# brainslug_board_1.net
KiCad netlist of a schematic drawn in EAGLE
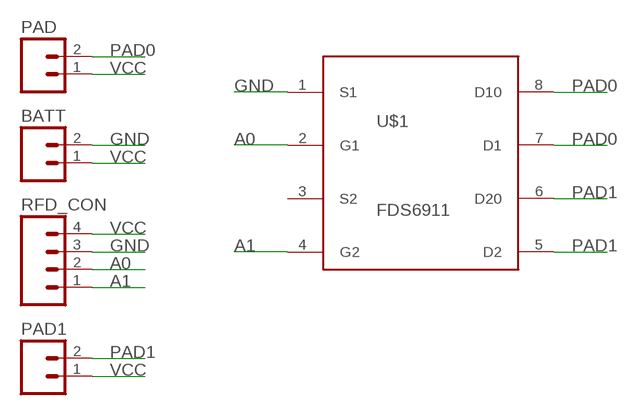
[diagram p0: schematic, sheet 1]

(export (version "E")
  (design (tool "Eeschema 10.0.6"))
  (components
    (comp (ref "BATT")
      (value "M02PTH")
      (footprint "eagle-import:1X02")
      (libsource (lib "eagle-import") (part "M02PTH"))
    )
    (comp (ref "PAD")
      (value "M02PTH")
      (footprint "eagle-import:1X02")
      (libsource (lib "eagle-import") (part "M02PTH"))
    )
    (comp (ref "PAD1")
      (value "M02PTH")
      (footprint "eagle-import:1X02")
      (libsource (lib "eagle-import") (part "M02PTH"))
    )
    (comp (ref "RFD_CON")
      (value "M04PTH")
      (footprint "eagle-import:1X04")
      (libsource (lib "eagle-import") (part "M04PTH"))
    )
    (comp (ref "U$1")
      (value "FDS6911")
      (footprint "eagle-import:SO8")
      (libsource (lib "eagle-import") (part "FDS6911"))
    )
  )
  (nets
    (net (code "1") (name "/A0") (class "Default")
      (node (ref "RFD_CON") (pin "2") (pinfunction "2_2") (pintype "passive"))
      (node (ref "U$1") (pin "2") (pinfunction "G1_2") (pintype "bidirectional"))
    )
    (net (code "2") (name "/A1") (class "Default")
      (node (ref "RFD_CON") (pin "1") (pinfunction "1_1") (pintype "passive"))
      (node (ref "U$1") (pin "4") (pinfunction "G2_4") (pintype "bidirectional"))
    )
    (net (code "3") (name "/GND") (class "Default")
      (node (ref "BATT") (pin "2") (pinfunction "2_2") (pintype "passive"))
      (node (ref "RFD_CON") (pin "3") (pinfunction "3_3") (pintype "passive"))
      (node (ref "U$1") (pin "1") (pinfunction "S1_1") (pintype "bidirectional"))
    )
    (net (code "4") (name "/PAD0") (class "Default")
      (node (ref "PAD") (pin "2") (pinfunction "2_2") (pintype "passive"))
      (node (ref "U$1") (pin "7") (pinfunction "D1_7") (pintype "bidirectional"))
      (node (ref "U$1") (pin "8") (pinfunction "D10_8") (pintype "bidirectional"))
    )
    (net (code "5") (name "/PAD1") (class "Default")
      (node (ref "PAD1") (pin "2") (pinfunction "2_2") (pintype "passive"))
      (node (ref "U$1") (pin "5") (pinfunction "D2_5") (pintype "bidirectional"))
      (node (ref "U$1") (pin "6") (pinfunction "D20_6") (pintype "bidirectional"))
    )
    (net (code "6") (name "/VCC") (class "Default")
      (node (ref "BATT") (pin "1") (pinfunction "1_1") (pintype "passive"))
      (node (ref "PAD") (pin "1") (pinfunction "1_1") (pintype "passive"))
      (node (ref "PAD1") (pin "1") (pinfunction "1_1") (pintype "passive"))
      (node (ref "RFD_CON") (pin "4") (pinfunction "4_4") (pintype "passive"))
    )
    (net (code "7") (name "unconnected-(U$1-S2-Pad3)") (class "Default")
      (node (ref "U$1") (pin "3") (pinfunction "S2_3") (pintype "bidirectional"))
    )
  )
)
